# inKard-Link.net
KiCad netlist of a schematic drawn in Altium Designer
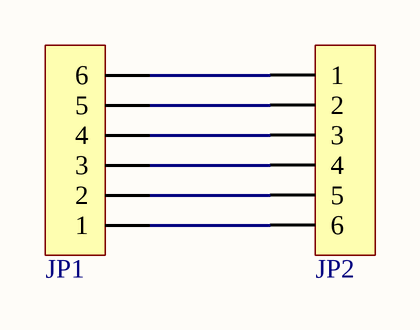
[diagram p0: inKard-Link.SchDoc]

(export (version "E")
  (design (tool "Eeschema 10.0.6"))
  (components
    (comp (ref "JP1")
      (value "HDR-1X6")
      (footprint "HDR2.54-M-LI-6P")
      (description "6P接插件")
      (fields (field (name "版权归属") "源创客"))
      (libsource (lib "4.6   - 接插件-脚距2.54") (part "Header 6"))
    )
    (comp (ref "JP2")
      (value "HDR-1X6")
      (footprint "HDR1.27-LI-6P")
      (description "6P接插件")
      (fields (field (name "版权归属") "源创客"))
      (libsource (lib "4.3   - 接插件-脚距1.27") (part "Header 6"))
    )
  )
  (nets
    (net (code "1") (name "Net-(JP1-Pad1)") (class "Default")
      (node (ref "JP1") (pin "1") (pinfunction "1_1") (pintype "passive"))
      (node (ref "JP2") (pin "6") (pinfunction "6_6") (pintype "passive"))
    )
    (net (code "2") (name "Net-(JP1-Pad2)") (class "Default")
      (node (ref "JP1") (pin "2") (pinfunction "2_2") (pintype "passive"))
      (node (ref "JP2") (pin "5") (pinfunction "5_5") (pintype "passive"))
    )
    (net (code "3") (name "Net-(JP1-Pad3)") (class "Default")
      (node (ref "JP1") (pin "3") (pinfunction "3_3") (pintype "passive"))
      (node (ref "JP2") (pin "4") (pinfunction "4_4") (pintype "passive"))
    )
    (net (code "4") (name "Net-(JP1-Pad4)") (class "Default")
      (node (ref "JP1") (pin "4") (pinfunction "4_4") (pintype "passive"))
      (node (ref "JP2") (pin "3") (pinfunction "3_3") (pintype "passive"))
    )
    (net (code "5") (name "Net-(JP1-Pad5)") (class "Default")
      (node (ref "JP1") (pin "5") (pinfunction "5_5") (pintype "passive"))
      (node (ref "JP2") (pin "2") (pinfunction "2_2") (pintype "passive"))
    )
    (net (code "6") (name "Net-(JP1-Pad6)") (class "Default")
      (node (ref "JP1") (pin "6") (pinfunction "6_6") (pintype "passive"))
      (node (ref "JP2") (pin "1") (pinfunction "1_1") (pintype "passive"))
    )
  )
)
